# Backplane_extRefV3.net
KiCad netlist of a schematic drawn in EAGLE
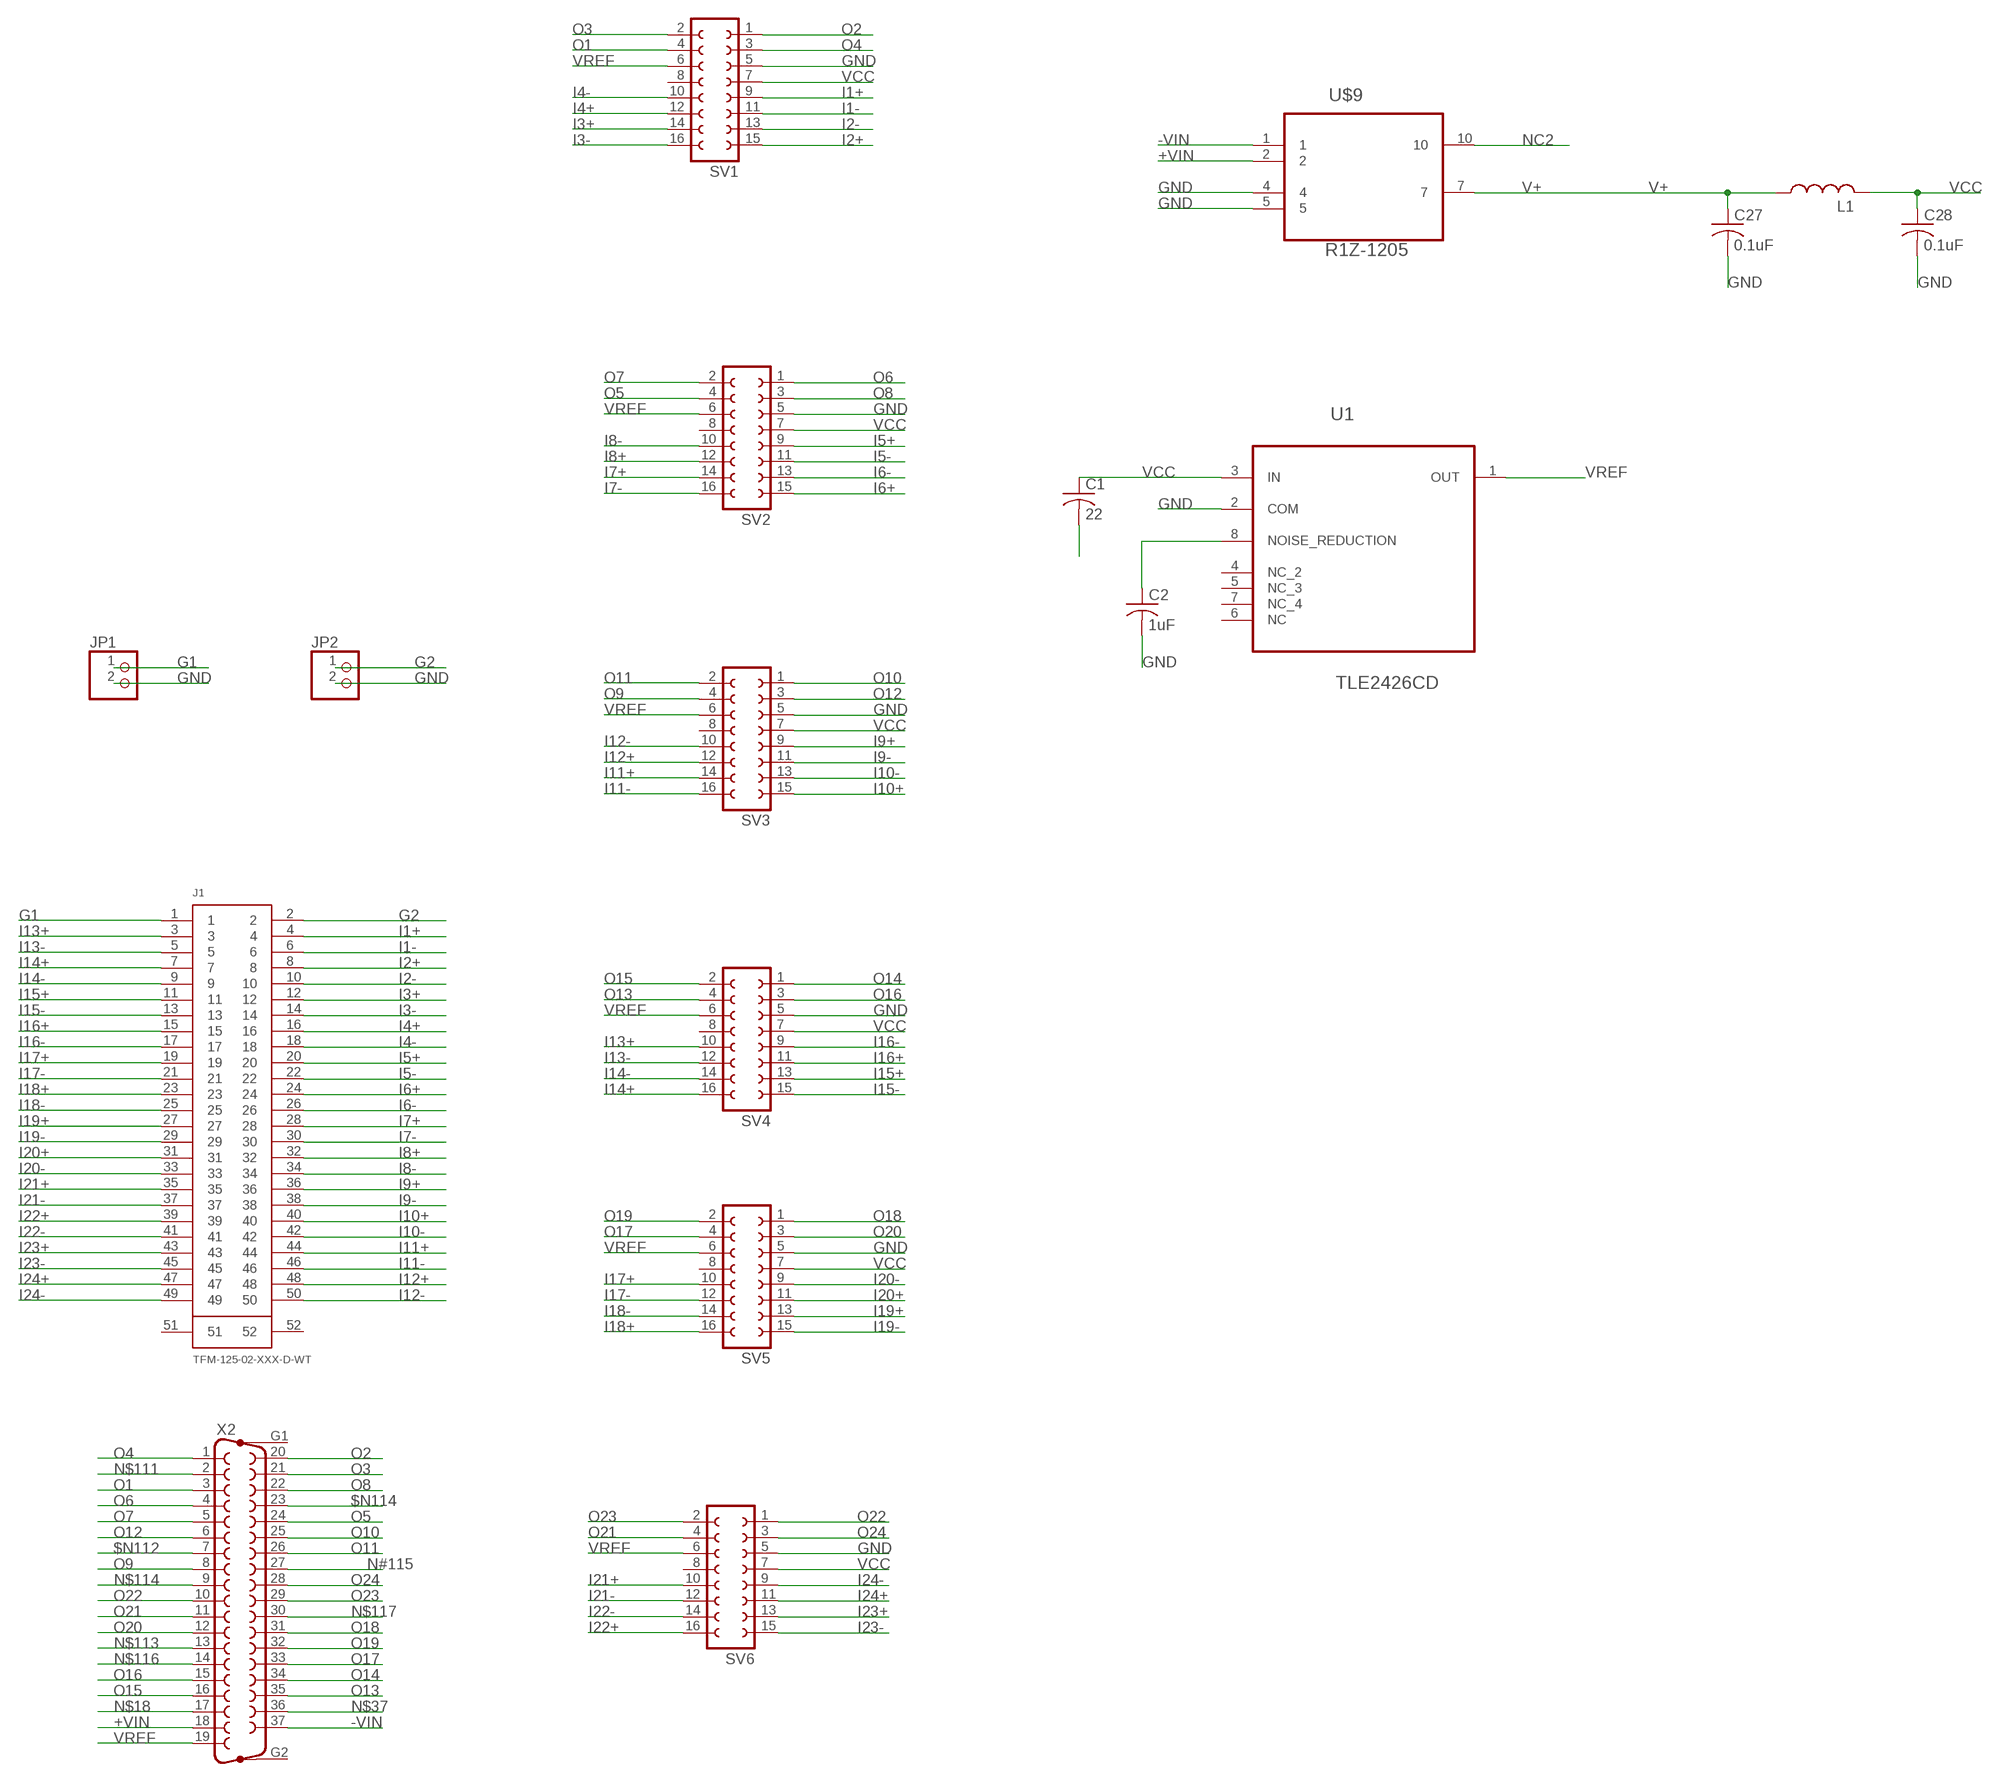
[diagram p0: schematic, sheet 1]

(export (version "E")
  (design (tool "Eeschema 10.0.6"))
  (components
    (comp (ref "C1")
      (value "22")
      (footprint "eagle-import:C0805")
      (libsource (lib "eagle-import") (part "C-USC0805"))
    )
    (comp (ref "C2")
      (value "1uF")
      (footprint "eagle-import:C0805")
      (libsource (lib "eagle-import") (part "C-USC0805"))
    )
    (comp (ref "C27")
      (value "0.1uF")
      (footprint "eagle-import:C0805")
      (libsource (lib "eagle-import") (part "C-USC0805"))
    )
    (comp (ref "C28")
      (value "0.1uF")
      (footprint "eagle-import:C0805")
      (libsource (lib "eagle-import") (part "C-USC0805"))
    )
    (comp (ref "J1")
      (value "TFM-125-02-XXX-D-WT")
      (footprint "eagle-import:TFM-125-02-XXX-D-WT")
      (libsource (lib "eagle-import") (part "TFM-125-02-XXX-D-WT"))
    )
    (comp (ref "JP1")
      (value "PINHD-1X2")
      (footprint "eagle-import:1X02")
      (libsource (lib "eagle-import") (part "PINHD-1X2"))
    )
    (comp (ref "JP2")
      (value "PINHD-1X2")
      (footprint "eagle-import:1X02")
      (libsource (lib "eagle-import") (part "PINHD-1X2"))
    )
    (comp (ref "L1")
      (value "L-USL3225M")
      (footprint "eagle-import:L3225M")
      (libsource (lib "eagle-import") (part "L-USL3225M"))
    )
    (comp (ref "SV1")
      (value "FE08-2")
      (footprint "eagle-import:FE08-2")
      (libsource (lib "eagle-import") (part "FE08-2"))
    )
    (comp (ref "SV2")
      (value "FE08-2")
      (footprint "eagle-import:FE08-2")
      (libsource (lib "eagle-import") (part "FE08-2"))
    )
    (comp (ref "SV3")
      (value "FE08-2")
      (footprint "eagle-import:FE08-2")
      (libsource (lib "eagle-import") (part "FE08-2"))
    )
    (comp (ref "SV4")
      (value "FE08-2")
      (footprint "eagle-import:FE08-2")
      (libsource (lib "eagle-import") (part "FE08-2"))
    )
    (comp (ref "SV5")
      (value "FE08-2")
      (footprint "eagle-import:FE08-2")
      (libsource (lib "eagle-import") (part "FE08-2"))
    )
    (comp (ref "SV6")
      (value "FE08-2")
      (footprint "eagle-import:FE08-2")
      (libsource (lib "eagle-import") (part "FE08-2"))
    )
    (comp (ref "U$9")
      (value "R1Z-1205")
      (footprint "eagle-import:R1Z-1205")
      (libsource (lib "eagle-import") (part "R1Z-1205"))
    )
    (comp (ref "U1")
      (value "TLE2426CD")
      (footprint "eagle-import:SOIC127P600X175-8N")
      (libsource (lib "eagle-import") (part "TLE2426CD"))
    )
    (comp (ref "X2")
      (value "F37HP")
      (footprint "eagle-import:F37HP")
      (libsource (lib "eagle-import") (part "F37HP"))
    )
  )
  (nets
    (net (code "1") (name "/$N112") (class "Default")
      (node (ref "X2") (pin "7") (pinfunction "7_7") (pintype "passive"))
    )
    (net (code "2") (name "/$N114") (class "Default")
      (node (ref "X2") (pin "23") (pinfunction "23_23") (pintype "passive"))
    )
    (net (code "3") (name "/+VIN") (class "Default")
      (node (ref "U$9") (pin "2") (pinfunction "2_2") (pintype "passive"))
      (node (ref "X2") (pin "18") (pinfunction "18_18") (pintype "passive"))
    )
    (net (code "4") (name "/-VIN") (class "Default")
      (node (ref "U$9") (pin "1") (pinfunction "1_1") (pintype "passive"))
      (node (ref "X2") (pin "37") (pinfunction "37_37") (pintype "passive"))
    )
    (net (code "5") (name "/G1") (class "Default")
      (node (ref "J1") (pin "1") (pinfunction "1_1") (pintype "bidirectional"))
      (node (ref "JP1") (pin "1") (pinfunction "1_1") (pintype "passive"))
    )
    (net (code "6") (name "/G2") (class "Default")
      (node (ref "J1") (pin "2") (pinfunction "2_2") (pintype "bidirectional"))
      (node (ref "JP2") (pin "1") (pinfunction "1_1") (pintype "passive"))
    )
    (net (code "7") (name "/GND") (class "Default")
      (node (ref "C1") (pin "2") (pinfunction "2_2") (pintype "passive"))
      (node (ref "C2") (pin "2") (pinfunction "2_2") (pintype "passive"))
      (node (ref "C27") (pin "2") (pinfunction "2_2") (pintype "passive"))
      (node (ref "C28") (pin "2") (pinfunction "2_2") (pintype "passive"))
      (node (ref "JP1") (pin "2") (pinfunction "2_2") (pintype "passive"))
      (node (ref "JP2") (pin "2") (pinfunction "2_2") (pintype "passive"))
      (node (ref "SV1") (pin "5") (pinfunction "5_5") (pintype "passive"))
      (node (ref "SV2") (pin "5") (pinfunction "5_5") (pintype "passive"))
      (node (ref "SV3") (pin "5") (pinfunction "5_5") (pintype "passive"))
      (node (ref "SV4") (pin "5") (pinfunction "5_5") (pintype "passive"))
      (node (ref "SV5") (pin "5") (pinfunction "5_5") (pintype "passive"))
      (node (ref "SV6") (pin "5") (pinfunction "5_5") (pintype "passive"))
      (node (ref "U$9") (pin "4") (pinfunction "4_4") (pintype "passive"))
      (node (ref "U$9") (pin "5") (pinfunction "5_5") (pintype "passive"))
      (node (ref "U1") (pin "2") (pinfunction "COM_2") (pintype "passive"))
    )
    (net (code "8") (name "/I1+") (class "Default")
      (node (ref "J1") (pin "4") (pinfunction "4_4") (pintype "bidirectional"))
      (node (ref "SV1") (pin "9") (pinfunction "9_9") (pintype "passive"))
    )
    (net (code "9") (name "/I1-") (class "Default")
      (node (ref "J1") (pin "6") (pinfunction "6_6") (pintype "bidirectional"))
      (node (ref "SV1") (pin "11") (pinfunction "11_11") (pintype "passive"))
    )
    (net (code "10") (name "/I2+") (class "Default")
      (node (ref "J1") (pin "8") (pinfunction "8_8") (pintype "bidirectional"))
      (node (ref "SV1") (pin "15") (pinfunction "15_15") (pintype "passive"))
    )
    (net (code "11") (name "/I2-") (class "Default")
      (node (ref "J1") (pin "10") (pinfunction "10_10") (pintype "bidirectional"))
      (node (ref "SV1") (pin "13") (pinfunction "13_13") (pintype "passive"))
    )
    (net (code "12") (name "/I3+") (class "Default")
      (node (ref "J1") (pin "12") (pinfunction "12_12") (pintype "bidirectional"))
      (node (ref "SV1") (pin "14") (pinfunction "14_14") (pintype "passive"))
    )
    (net (code "13") (name "/I3-") (class "Default")
      (node (ref "J1") (pin "14") (pinfunction "14_14") (pintype "bidirectional"))
      (node (ref "SV1") (pin "16") (pinfunction "16_16") (pintype "passive"))
    )
    (net (code "14") (name "/I4+") (class "Default")
      (node (ref "J1") (pin "16") (pinfunction "16_16") (pintype "bidirectional"))
      (node (ref "SV1") (pin "12") (pinfunction "12_12") (pintype "passive"))
    )
    (net (code "15") (name "/I4-") (class "Default")
      (node (ref "J1") (pin "18") (pinfunction "18_18") (pintype "bidirectional"))
      (node (ref "SV1") (pin "10") (pinfunction "10_10") (pintype "passive"))
    )
    (net (code "16") (name "/I5+") (class "Default")
      (node (ref "J1") (pin "20") (pinfunction "20_20") (pintype "bidirectional"))
      (node (ref "SV2") (pin "9") (pinfunction "9_9") (pintype "passive"))
    )
    (net (code "17") (name "/I5-") (class "Default")
      (node (ref "J1") (pin "22") (pinfunction "22_22") (pintype "bidirectional"))
      (node (ref "SV2") (pin "11") (pinfunction "11_11") (pintype "passive"))
    )
    (net (code "18") (name "/I6+") (class "Default")
      (node (ref "J1") (pin "24") (pinfunction "24_24") (pintype "bidirectional"))
      (node (ref "SV2") (pin "15") (pinfunction "15_15") (pintype "passive"))
    )
    (net (code "19") (name "/I6-") (class "Default")
      (node (ref "J1") (pin "26") (pinfunction "26_26") (pintype "bidirectional"))
      (node (ref "SV2") (pin "13") (pinfunction "13_13") (pintype "passive"))
    )
    (net (code "20") (name "/I7+") (class "Default")
      (node (ref "J1") (pin "28") (pinfunction "28_28") (pintype "bidirectional"))
      (node (ref "SV2") (pin "14") (pinfunction "14_14") (pintype "passive"))
    )
    (net (code "21") (name "/I7-") (class "Default")
      (node (ref "J1") (pin "30") (pinfunction "30_30") (pintype "bidirectional"))
      (node (ref "SV2") (pin "16") (pinfunction "16_16") (pintype "passive"))
    )
    (net (code "22") (name "/I8+") (class "Default")
      (node (ref "J1") (pin "32") (pinfunction "32_32") (pintype "bidirectional"))
      (node (ref "SV2") (pin "12") (pinfunction "12_12") (pintype "passive"))
    )
    (net (code "23") (name "/I8-") (class "Default")
      (node (ref "J1") (pin "34") (pinfunction "34_34") (pintype "bidirectional"))
      (node (ref "SV2") (pin "10") (pinfunction "10_10") (pintype "passive"))
    )
    (net (code "24") (name "/I9+") (class "Default")
      (node (ref "J1") (pin "36") (pinfunction "36_36") (pintype "bidirectional"))
      (node (ref "SV3") (pin "9") (pinfunction "9_9") (pintype "passive"))
    )
    (net (code "25") (name "/I9-") (class "Default")
      (node (ref "J1") (pin "38") (pinfunction "38_38") (pintype "bidirectional"))
      (node (ref "SV3") (pin "11") (pinfunction "11_11") (pintype "passive"))
    )
    (net (code "26") (name "/I10+") (class "Default")
      (node (ref "J1") (pin "40") (pinfunction "40_40") (pintype "bidirectional"))
      (node (ref "SV3") (pin "15") (pinfunction "15_15") (pintype "passive"))
    )
    (net (code "27") (name "/I10-") (class "Default")
      (node (ref "J1") (pin "42") (pinfunction "42_42") (pintype "bidirectional"))
      (node (ref "SV3") (pin "13") (pinfunction "13_13") (pintype "passive"))
    )
    (net (code "28") (name "/I11+") (class "Default")
      (node (ref "J1") (pin "44") (pinfunction "44_44") (pintype "bidirectional"))
      (node (ref "SV3") (pin "14") (pinfunction "14_14") (pintype "passive"))
    )
    (net (code "29") (name "/I11-") (class "Default")
      (node (ref "J1") (pin "46") (pinfunction "46_46") (pintype "bidirectional"))
      (node (ref "SV3") (pin "16") (pinfunction "16_16") (pintype "passive"))
    )
    (net (code "30") (name "/I12+") (class "Default")
      (node (ref "J1") (pin "48") (pinfunction "48_48") (pintype "bidirectional"))
      (node (ref "SV3") (pin "12") (pinfunction "12_12") (pintype "passive"))
    )
    (net (code "31") (name "/I12-") (class "Default")
      (node (ref "J1") (pin "50") (pinfunction "50_50") (pintype "bidirectional"))
      (node (ref "SV3") (pin "10") (pinfunction "10_10") (pintype "passive"))
    )
    (net (code "32") (name "/I13+") (class "Default")
      (node (ref "J1") (pin "3") (pinfunction "3_3") (pintype "bidirectional"))
      (node (ref "SV4") (pin "10") (pinfunction "10_10") (pintype "passive"))
    )
    (net (code "33") (name "/I13-") (class "Default")
      (node (ref "J1") (pin "5") (pinfunction "5_5") (pintype "bidirectional"))
      (node (ref "SV4") (pin "12") (pinfunction "12_12") (pintype "passive"))
    )
    (net (code "34") (name "/I14+") (class "Default")
      (node (ref "J1") (pin "7") (pinfunction "7_7") (pintype "bidirectional"))
      (node (ref "SV4") (pin "16") (pinfunction "16_16") (pintype "passive"))
    )
    (net (code "35") (name "/I14-") (class "Default")
      (node (ref "J1") (pin "9") (pinfunction "9_9") (pintype "bidirectional"))
      (node (ref "SV4") (pin "14") (pinfunction "14_14") (pintype "passive"))
    )
    (net (code "36") (name "/I15+") (class "Default")
      (node (ref "J1") (pin "11") (pinfunction "11_11") (pintype "bidirectional"))
      (node (ref "SV4") (pin "13") (pinfunction "13_13") (pintype "passive"))
    )
    (net (code "37") (name "/I15-") (class "Default")
      (node (ref "J1") (pin "13") (pinfunction "13_13") (pintype "bidirectional"))
      (node (ref "SV4") (pin "15") (pinfunction "15_15") (pintype "passive"))
    )
    (net (code "38") (name "/I16+") (class "Default")
      (node (ref "J1") (pin "15") (pinfunction "15_15") (pintype "bidirectional"))
      (node (ref "SV4") (pin "11") (pinfunction "11_11") (pintype "passive"))
    )
    (net (code "39") (name "/I16-") (class "Default")
      (node (ref "J1") (pin "17") (pinfunction "17_17") (pintype "bidirectional"))
      (node (ref "SV4") (pin "9") (pinfunction "9_9") (pintype "passive"))
    )
    (net (code "40") (name "/I17+") (class "Default")
      (node (ref "J1") (pin "19") (pinfunction "19_19") (pintype "bidirectional"))
      (node (ref "SV5") (pin "10") (pinfunction "10_10") (pintype "passive"))
    )
    (net (code "41") (name "/I17-") (class "Default")
      (node (ref "J1") (pin "21") (pinfunction "21_21") (pintype "bidirectional"))
      (node (ref "SV5") (pin "12") (pinfunction "12_12") (pintype "passive"))
    )
    (net (code "42") (name "/I18+") (class "Default")
      (node (ref "J1") (pin "23") (pinfunction "23_23") (pintype "bidirectional"))
      (node (ref "SV5") (pin "16") (pinfunction "16_16") (pintype "passive"))
    )
    (net (code "43") (name "/I18-") (class "Default")
      (node (ref "J1") (pin "25") (pinfunction "25_25") (pintype "bidirectional"))
      (node (ref "SV5") (pin "14") (pinfunction "14_14") (pintype "passive"))
    )
    (net (code "44") (name "/I19+") (class "Default")
      (node (ref "J1") (pin "27") (pinfunction "27_27") (pintype "bidirectional"))
      (node (ref "SV5") (pin "13") (pinfunction "13_13") (pintype "passive"))
    )
    (net (code "45") (name "/I19-") (class "Default")
      (node (ref "J1") (pin "29") (pinfunction "29_29") (pintype "bidirectional"))
      (node (ref "SV5") (pin "15") (pinfunction "15_15") (pintype "passive"))
    )
    (net (code "46") (name "/I20+") (class "Default")
      (node (ref "J1") (pin "31") (pinfunction "31_31") (pintype "bidirectional"))
      (node (ref "SV5") (pin "11") (pinfunction "11_11") (pintype "passive"))
    )
    (net (code "47") (name "/I20-") (class "Default")
      (node (ref "J1") (pin "33") (pinfunction "33_33") (pintype "bidirectional"))
      (node (ref "SV5") (pin "9") (pinfunction "9_9") (pintype "passive"))
    )
    (net (code "48") (name "/I21+") (class "Default")
      (node (ref "J1") (pin "35") (pinfunction "35_35") (pintype "bidirectional"))
      (node (ref "SV6") (pin "10") (pinfunction "10_10") (pintype "passive"))
    )
    (net (code "49") (name "/I21-") (class "Default")
      (node (ref "J1") (pin "37") (pinfunction "37_37") (pintype "bidirectional"))
      (node (ref "SV6") (pin "12") (pinfunction "12_12") (pintype "passive"))
    )
    (net (code "50") (name "/I22+") (class "Default")
      (node (ref "J1") (pin "39") (pinfunction "39_39") (pintype "bidirectional"))
      (node (ref "SV6") (pin "16") (pinfunction "16_16") (pintype "passive"))
    )
    (net (code "51") (name "/I22-") (class "Default")
      (node (ref "J1") (pin "41") (pinfunction "41_41") (pintype "bidirectional"))
      (node (ref "SV6") (pin "14") (pinfunction "14_14") (pintype "passive"))
    )
    (net (code "52") (name "/I23+") (class "Default")
      (node (ref "J1") (pin "43") (pinfunction "43_43") (pintype "bidirectional"))
      (node (ref "SV6") (pin "13") (pinfunction "13_13") (pintype "passive"))
    )
    (net (code "53") (name "/I23-") (class "Default")
      (node (ref "J1") (pin "45") (pinfunction "45_45") (pintype "bidirectional"))
      (node (ref "SV6") (pin "15") (pinfunction "15_15") (pintype "passive"))
    )
    (net (code "54") (name "/I24+") (class "Default")
      (node (ref "J1") (pin "47") (pinfunction "47_47") (pintype "bidirectional"))
      (node (ref "SV6") (pin "11") (pinfunction "11_11") (pintype "passive"))
    )
    (net (code "55") (name "/I24-") (class "Default")
      (node (ref "J1") (pin "49") (pinfunction "49_49") (pintype "bidirectional"))
      (node (ref "SV6") (pin "9") (pinfunction "9_9") (pintype "passive"))
    )
    (net (code "56") (name "/N#115") (class "Default")
      (node (ref "X2") (pin "27") (pinfunction "27_27") (pintype "passive"))
    )
    (net (code "57") (name "/N$18") (class "Default")
      (node (ref "X2") (pin "17") (pinfunction "17_17") (pintype "passive"))
    )
    (net (code "58") (name "/N$37") (class "Default")
      (node (ref "X2") (pin "36") (pinfunction "36_36") (pintype "passive"))
    )
    (net (code "59") (name "/N$111") (class "Default")
      (node (ref "X2") (pin "2") (pinfunction "2_2") (pintype "passive"))
    )
    (net (code "60") (name "/N$113") (class "Default")
      (node (ref "X2") (pin "13") (pinfunction "13_13") (pintype "passive"))
    )
    (net (code "61") (name "/N$114") (class "Default")
      (node (ref "X2") (pin "9") (pinfunction "9_9") (pintype "passive"))
    )
    (net (code "62") (name "/N$116") (class "Default")
      (node (ref "X2") (pin "14") (pinfunction "14_14") (pintype "passive"))
    )
    (net (code "63") (name "/N$117") (class "Default")
      (node (ref "X2") (pin "30") (pinfunction "30_30") (pintype "passive"))
    )
    (net (code "64") (name "/NC2") (class "Default")
      (node (ref "U$9") (pin "10") (pinfunction "10_10") (pintype "passive"))
    )
    (net (code "65") (name "/O1") (class "Default")
      (node (ref "SV1") (pin "4") (pinfunction "4_4") (pintype "passive"))
      (node (ref "X2") (pin "3") (pinfunction "3_3") (pintype "passive"))
    )
    (net (code "66") (name "/O2") (class "Default")
      (node (ref "SV1") (pin "1") (pinfunction "1_1") (pintype "passive"))
      (node (ref "X2") (pin "20") (pinfunction "20_20") (pintype "passive"))
    )
    (net (code "67") (name "/O3") (class "Default")
      (node (ref "SV1") (pin "2") (pinfunction "2_2") (pintype "passive"))
      (node (ref "X2") (pin "21") (pinfunction "21_21") (pintype "passive"))
    )
    (net (code "68") (name "/O4") (class "Default")
      (node (ref "SV1") (pin "3") (pinfunction "3_3") (pintype "passive"))
      (node (ref "X2") (pin "1") (pinfunction "1_1") (pintype "passive"))
    )
    (net (code "69") (name "/O5") (class "Default")
      (node (ref "SV2") (pin "4") (pinfunction "4_4") (pintype "passive"))
      (node (ref "X2") (pin "24") (pinfunction "24_24") (pintype "passive"))
    )
    (net (code "70") (name "/O6") (class "Default")
      (node (ref "SV2") (pin "1") (pinfunction "1_1") (pintype "passive"))
      (node (ref "X2") (pin "4") (pinfunction "4_4") (pintype "passive"))
    )
    (net (code "71") (name "/O7") (class "Default")
      (node (ref "SV2") (pin "2") (pinfunction "2_2") (pintype "passive"))
      (node (ref "X2") (pin "5") (pinfunction "5_5") (pintype "passive"))
    )
    (net (code "72") (name "/O8") (class "Default")
      (node (ref "SV2") (pin "3") (pinfunction "3_3") (pintype "passive"))
      (node (ref "X2") (pin "22") (pinfunction "22_22") (pintype "passive"))
    )
    (net (code "73") (name "/O9") (class "Default")
      (node (ref "SV3") (pin "4") (pinfunction "4_4") (pintype "passive"))
      (node (ref "X2") (pin "8") (pinfunction "8_8") (pintype "passive"))
    )
    (net (code "74") (name "/O10") (class "Default")
      (node (ref "SV3") (pin "1") (pinfunction "1_1") (pintype "passive"))
      (node (ref "X2") (pin "25") (pinfunction "25_25") (pintype "passive"))
    )
    (net (code "75") (name "/O11") (class "Default")
      (node (ref "SV3") (pin "2") (pinfunction "2_2") (pintype "passive"))
      (node (ref "X2") (pin "26") (pinfunction "26_26") (pintype "passive"))
    )
    (net (code "76") (name "/O12") (class "Default")
      (node (ref "SV3") (pin "3") (pinfunction "3_3") (pintype "passive"))
      (node (ref "X2") (pin "6") (pinfunction "6_6") (pintype "passive"))
    )
    (net (code "77") (name "/O13") (class "Default")
      (node (ref "SV4") (pin "4") (pinfunction "4_4") (pintype "passive"))
      (node (ref "X2") (pin "35") (pinfunction "35_35") (pintype "passive"))
    )
    (net (code "78") (name "/O14") (class "Default")
      (node (ref "SV4") (pin "1") (pinfunction "1_1") (pintype "passive"))
      (node (ref "X2") (pin "34") (pinfunction "34_34") (pintype "passive"))
    )
    (net (code "79") (name "/O15") (class "Default")
      (node (ref "SV4") (pin "2") (pinfunction "2_2") (pintype "passive"))
      (node (ref "X2") (pin "16") (pinfunction "16_16") (pintype "passive"))
    )
    (net (code "80") (name "/O16") (class "Default")
      (node (ref "SV4") (pin "3") (pinfunction "3_3") (pintype "passive"))
      (node (ref "X2") (pin "15") (pinfunction "15_15") (pintype "passive"))
    )
    (net (code "81") (name "/O17") (class "Default")
      (node (ref "SV5") (pin "4") (pinfunction "4_4") (pintype "passive"))
      (node (ref "X2") (pin "33") (pinfunction "33_33") (pintype "passive"))
    )
    (net (code "82") (name "/O18") (class "Default")
      (node (ref "SV5") (pin "1") (pinfunction "1_1") (pintype "passive"))
      (node (ref "X2") (pin "31") (pinfunction "31_31") (pintype "passive"))
    )
    (net (code "83") (name "/O19") (class "Default")
      (node (ref "SV5") (pin "2") (pinfunction "2_2") (pintype "passive"))
      (node (ref "X2") (pin "32") (pinfunction "32_32") (pintype "passive"))
    )
    (net (code "84") (name "/O20") (class "Default")
      (node (ref "SV5") (pin "3") (pinfunction "3_3") (pintype "passive"))
      (node (ref "X2") (pin "12") (pinfunction "12_12") (pintype "passive"))
    )
    (net (code "85") (name "/O21") (class "Default")
      (node (ref "SV6") (pin "4") (pinfunction "4_4") (pintype "passive"))
      (node (ref "X2") (pin "11") (pinfunction "11_11") (pintype "passive"))
    )
    (net (code "86") (name "/O22") (class "Default")
      (node (ref "SV6") (pin "1") (pinfunction "1_1") (pintype "passive"))
      (node (ref "X2") (pin "10") (pinfunction "10_10") (pintype "passive"))
    )
    (net (code "87") (name "/O23") (class "Default")
      (node (ref "SV6") (pin "2") (pinfunction "2_2") (pintype "passive"))
      (node (ref "X2") (pin "29") (pinfunction "29_29") (pintype "passive"))
    )
    (net (code "88") (name "/O24") (class "Default")
      (node (ref "SV6") (pin "3") (pinfunction "3_3") (pintype "passive"))
      (node (ref "X2") (pin "28") (pinfunction "28_28") (pintype "passive"))
    )
    (net (code "89") (name "/V+") (class "Default")
      (node (ref "C27") (pin "1") (pinfunction "1_1") (pintype "passive"))
      (node (ref "L1") (pin "1") (pinfunction "1_1") (pintype "passive"))
      (node (ref "U$9") (pin "7") (pinfunction "7_7") (pintype "passive"))
    )
    (net (code "90") (name "/VCC") (class "Default")
      (node (ref "C1") (pin "1") (pinfunction "1_1") (pintype "passive"))
      (node (ref "C28") (pin "1") (pinfunction "1_1") (pintype "passive"))
      (node (ref "L1") (pin "2") (pinfunction "2_2") (pintype "passive"))
      (node (ref "SV1") (pin "7") (pinfunction "7_7") (pintype "passive"))
      (node (ref "SV2") (pin "7") (pinfunction "7_7") (pintype "passive"))
      (node (ref "SV3") (pin "7") (pinfunction "7_7") (pintype "passive"))
      (node (ref "SV4") (pin "7") (pinfunction "7_7") (pintype "passive"))
      (node (ref "SV5") (pin "7") (pinfunction "7_7") (pintype "passive"))
      (node (ref "SV6") (pin "7") (pinfunction "7_7") (pintype "passive"))
      (node (ref "U1") (pin "3") (pinfunction "IN_3") (pintype "input"))
    )
    (net (code "91") (name "/VREF") (class "Default")
      (node (ref "SV1") (pin "6") (pinfunction "6_6") (pintype "passive"))
      (node (ref "SV2") (pin "6") (pinfunction "6_6") (pintype "passive"))
      (node (ref "SV3") (pin "6") (pinfunction "6_6") (pintype "passive"))
      (node (ref "SV4") (pin "6") (pinfunction "6_6") (pintype "passive"))
      (node (ref "SV5") (pin "6") (pinfunction "6_6") (pintype "passive"))
      (node (ref "SV6") (pin "6") (pinfunction "6_6") (pintype "passive"))
      (node (ref "U1") (pin "1") (pinfunction "OUT_1") (pintype "output"))
      (node (ref "X2") (pin "19") (pinfunction "19_19") (pintype "passive"))
    )
    (net (code "92") (name "Net-(U1-NOISE_REDUCTION)") (class "Default")
      (node (ref "C2") (pin "1") (pinfunction "1_1") (pintype "passive"))
      (node (ref "U1") (pin "8") (pinfunction "NOISE_REDUCTION_8") (pintype "passive"))
    )
    (net (code "93") (name "unconnected-(J1-Pad51)") (class "Default")
      (node (ref "J1") (pin "51") (pinfunction "51_51") (pintype "bidirectional"))
    )
    (net (code "94") (name "unconnected-(J1-Pad52)") (class "Default")
      (node (ref "J1") (pin "52") (pinfunction "52_52") (pintype "bidirectional"))
    )
    (net (code "95") (name "unconnected-(SV1-Pad8)") (class "Default")
      (node (ref "SV1") (pin "8") (pinfunction "8_8") (pintype "passive"))
    )
    (net (code "96") (name "unconnected-(SV2-Pad8)") (class "Default")
      (node (ref "SV2") (pin "8") (pinfunction "8_8") (pintype "passive"))
    )
    (net (code "97") (name "unconnected-(SV3-Pad8)") (class "Default")
      (node (ref "SV3") (pin "8") (pinfunction "8_8") (pintype "passive"))
    )
    (net (code "98") (name "unconnected-(SV4-Pad8)") (class "Default")
      (node (ref "SV4") (pin "8") (pinfunction "8_8") (pintype "passive"))
    )
    (net (code "99") (name "unconnected-(SV5-Pad8)") (class "Default")
      (node (ref "SV5") (pin "8") (pinfunction "8_8") (pintype "passive"))
    )
    (net (code "100") (name "unconnected-(SV6-Pad8)") (class "Default")
      (node (ref "SV6") (pin "8") (pinfunction "8_8") (pintype "passive"))
    )
    (net (code "101") (name "unconnected-(U1-NC-Pad6)") (class "Default")
      (node (ref "U1") (pin "6") (pinfunction "NC_6") (pintype "no_connect"))
    )
    (net (code "102") (name "unconnected-(U1-NC_2-Pad4)") (class "Default")
      (node (ref "U1") (pin "4") (pinfunction "NC_2_4") (pintype "no_connect"))
    )
    (net (code "103") (name "unconnected-(U1-NC_3-Pad5)") (class "Default")
      (node (ref "U1") (pin "5") (pinfunction "NC_3_5") (pintype "no_connect"))
    )
    (net (code "104") (name "unconnected-(U1-NC_4-Pad7)") (class "Default")
      (node (ref "U1") (pin "7") (pinfunction "NC_4_7") (pintype "no_connect"))
    )
    (net (code "105") (name "unconnected-(X2-PadG1)") (class "Default")
      (node (ref "X2") (pin "G1") (pinfunction "G1_G1") (pintype "passive"))
    )
    (net (code "106") (name "unconnected-(X2-PadG2)") (class "Default")
      (node (ref "X2") (pin "G2") (pinfunction "G2_G2") (pintype "passive"))
    )
  )
)
